# imu.net
KiCad netlist of a schematic drawn in EAGLE
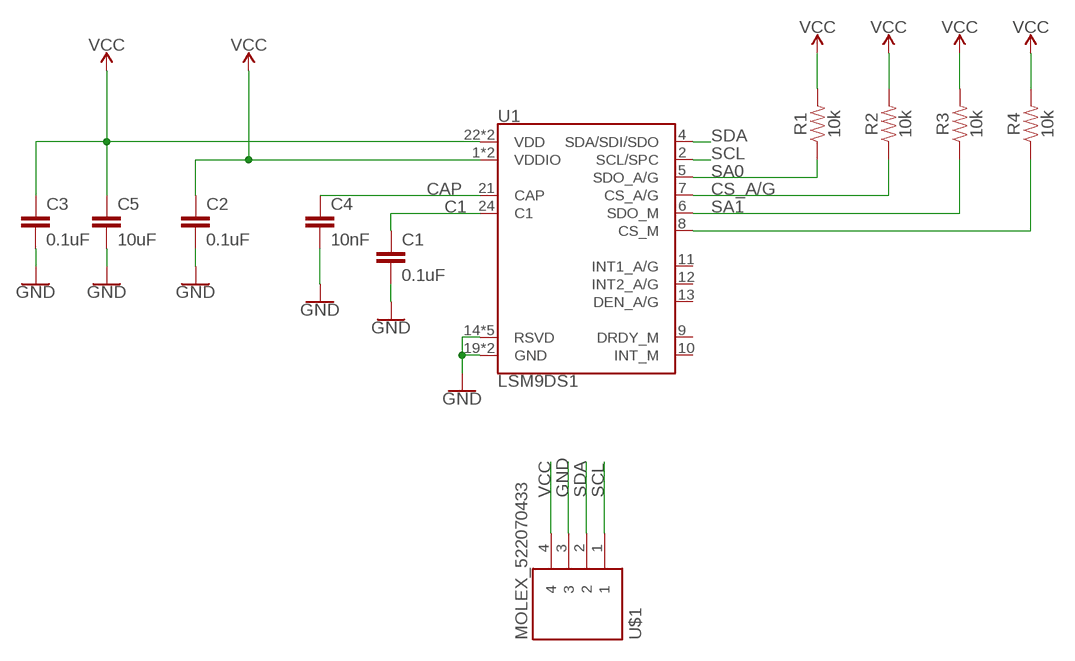
[diagram p0: schematic, sheet 1]

(export (version "E")
  (design (tool "Eeschema 10.0.6"))
  (components
    (comp (ref "C1")
      (value "0.1uF")
      (footprint "eagle-import:0603")
      (libsource (lib "eagle-import") (part "0.1UF-0603-25V-(+80/-20%)"))
    )
    (comp (ref "C2")
      (value "0.1uF")
      (footprint "eagle-import:0603")
      (libsource (lib "eagle-import") (part "0.1UF-0603-25V-(+80/-20%)"))
    )
    (comp (ref "C3")
      (value "0.1uF")
      (footprint "eagle-import:0603")
      (libsource (lib "eagle-import") (part "0.1UF-0603-25V-(+80/-20%)"))
    )
    (comp (ref "C4")
      (value "10nF")
      (footprint "eagle-import:0603")
      (libsource (lib "eagle-import") (part "10NF-0603-50V-10%"))
    )
    (comp (ref "C5")
      (value "10uF")
      (footprint "eagle-import:0603")
      (libsource (lib "eagle-import") (part "10UF-0603-6.3V-20%"))
    )
    (comp (ref "R1")
      (value "10k")
      (footprint "eagle-import:0603")
      (libsource (lib "eagle-import") (part "10KOHM-0603-1/10W-1%"))
    )
    (comp (ref "R2")
      (value "10k")
      (footprint "eagle-import:0603")
      (libsource (lib "eagle-import") (part "10KOHM-0603-1/10W-1%"))
    )
    (comp (ref "R3")
      (value "10k")
      (footprint "eagle-import:0603")
      (libsource (lib "eagle-import") (part "10KOHM-0603-1/10W-1%"))
    )
    (comp (ref "R4")
      (value "10k")
      (footprint "eagle-import:0603")
      (libsource (lib "eagle-import") (part "10KOHM-0603-1/10W-1%"))
    )
    (comp (ref "U$1")
      (value "MOLEX_522070433")
      (footprint "eagle-import:MOLEX4_1MM")
      (libsource (lib "eagle-import") (part "MOLEX_522070433"))
    )
    (comp (ref "U1")
      (value "LSM9DS1")
      (footprint "eagle-import:LGA-24-3.5X3")
      (libsource (lib "eagle-import") (part "LSM9DS1"))
    )
  )
  (nets
    (net (code "1") (name "/C1") (class "Default")
      (node (ref "C1") (pin "1") (pinfunction "1_1") (pintype "passive"))
      (node (ref "U1") (pin "24") (pinfunction "C1_24") (pintype "bidirectional"))
    )
    (net (code "2") (name "/CAP") (class "Default")
      (node (ref "C4") (pin "1") (pinfunction "1_1") (pintype "passive"))
      (node (ref "U1") (pin "21") (pinfunction "CAP_21") (pintype "bidirectional"))
    )
    (net (code "3") (name "/CS_A{slash}G") (class "Default")
      (node (ref "R2") (pin "1") (pinfunction "1_1") (pintype "passive"))
      (node (ref "U1") (pin "7") (pinfunction "CS_A/G_7") (pintype "bidirectional"))
    )
    (net (code "4") (name "/SA0") (class "Default")
      (node (ref "R1") (pin "1") (pinfunction "1_1") (pintype "passive"))
      (node (ref "U1") (pin "5") (pinfunction "SDO_A/G_5") (pintype "bidirectional"))
    )
    (net (code "5") (name "/SA1") (class "Default")
      (node (ref "R3") (pin "1") (pinfunction "1_1") (pintype "passive"))
      (node (ref "U1") (pin "6") (pinfunction "SDO_M_6") (pintype "bidirectional"))
    )
    (net (code "6") (name "/SCL") (class "Default")
      (node (ref "U$1") (pin "1") (pinfunction "1_1") (pintype "passive"))
      (node (ref "U1") (pin "2") (pinfunction "SCL/SPC_2") (pintype "bidirectional"))
    )
    (net (code "7") (name "/SDA") (class "Default")
      (node (ref "U$1") (pin "2") (pinfunction "2_2") (pintype "passive"))
      (node (ref "U1") (pin "4") (pinfunction "SDA/SDI/SDO_4") (pintype "bidirectional"))
    )
    (net (code "8") (name "GND") (class "Default")
      (node (ref "C1") (pin "2") (pinfunction "2_2") (pintype "passive"))
      (node (ref "C2") (pin "2") (pinfunction "2_2") (pintype "passive"))
      (node (ref "C3") (pin "2") (pinfunction "2_2") (pintype "passive"))
      (node (ref "C4") (pin "2") (pinfunction "2_2") (pintype "passive"))
      (node (ref "C5") (pin "2") (pinfunction "2_2") (pintype "passive"))
      (node (ref "U$1") (pin "3") (pinfunction "3_3") (pintype "passive"))
      (node (ref "U1") (pin "14") (pinfunction "RSVD_14") (pintype "bidirectional"))
      (node (ref "U1") (pin "15") (pinfunction "RSVD_15") (pintype "bidirectional"))
      (node (ref "U1") (pin "16") (pinfunction "RSVD_16") (pintype "bidirectional"))
      (node (ref "U1") (pin "17") (pinfunction "RSVD_17") (pintype "bidirectional"))
      (node (ref "U1") (pin "18") (pinfunction "RSVD_18") (pintype "bidirectional"))
      (node (ref "U1") (pin "19") (pinfunction "GND_19") (pintype "bidirectional"))
      (node (ref "U1") (pin "20") (pinfunction "GND_20") (pintype "bidirectional"))
    )
    (net (code "9") (name "Net-(U1-CS_M)") (class "Default")
      (node (ref "R4") (pin "1") (pinfunction "1_1") (pintype "passive"))
      (node (ref "U1") (pin "8") (pinfunction "CS_M_8") (pintype "bidirectional"))
    )
    (net (code "10") (name "VCC") (class "Default")
      (node (ref "C2") (pin "1") (pinfunction "1_1") (pintype "passive"))
      (node (ref "C3") (pin "1") (pinfunction "1_1") (pintype "passive"))
      (node (ref "C5") (pin "1") (pinfunction "1_1") (pintype "passive"))
      (node (ref "R1") (pin "2") (pinfunction "2_2") (pintype "passive"))
      (node (ref "R2") (pin "2") (pinfunction "2_2") (pintype "passive"))
      (node (ref "R3") (pin "2") (pinfunction "2_2") (pintype "passive"))
      (node (ref "R4") (pin "2") (pinfunction "2_2") (pintype "passive"))
      (node (ref "U$1") (pin "4") (pinfunction "4_4") (pintype "passive"))
      (node (ref "U1") (pin "1") (pinfunction "VDDIO_1") (pintype "bidirectional"))
      (node (ref "U1") (pin "22") (pinfunction "VDD_22") (pintype "bidirectional"))
      (node (ref "U1") (pin "23") (pinfunction "VDD_23") (pintype "bidirectional"))
      (node (ref "U1") (pin "3") (pinfunction "VDDIO_3") (pintype "bidirectional"))
    )
    (net (code "11") (name "unconnected-(U1-DEN_A{slash}G-Pad13)") (class "Default")
      (node (ref "U1") (pin "13") (pinfunction "DEN_A/G_13") (pintype "bidirectional"))
    )
    (net (code "12") (name "unconnected-(U1-DRDY_M-Pad9)") (class "Default")
      (node (ref "U1") (pin "9") (pinfunction "DRDY_M_9") (pintype "bidirectional"))
    )
    (net (code "13") (name "unconnected-(U1-INT1_A{slash}G-Pad11)") (class "Default")
      (node (ref "U1") (pin "11") (pinfunction "INT1_A/G_11") (pintype "bidirectional"))
    )
    (net (code "14") (name "unconnected-(U1-INT2_A{slash}G-Pad12)") (class "Default")
      (node (ref "U1") (pin "12") (pinfunction "INT2_A/G_12") (pintype "bidirectional"))
    )
    (net (code "15") (name "unconnected-(U1-INT_M-Pad10)") (class "Default")
      (node (ref "U1") (pin "10") (pinfunction "INT_M_10") (pintype "bidirectional"))
    )
  )
)
